# Voltage_source.net
KiCad netlist of a schematic drawn in Altium Designer
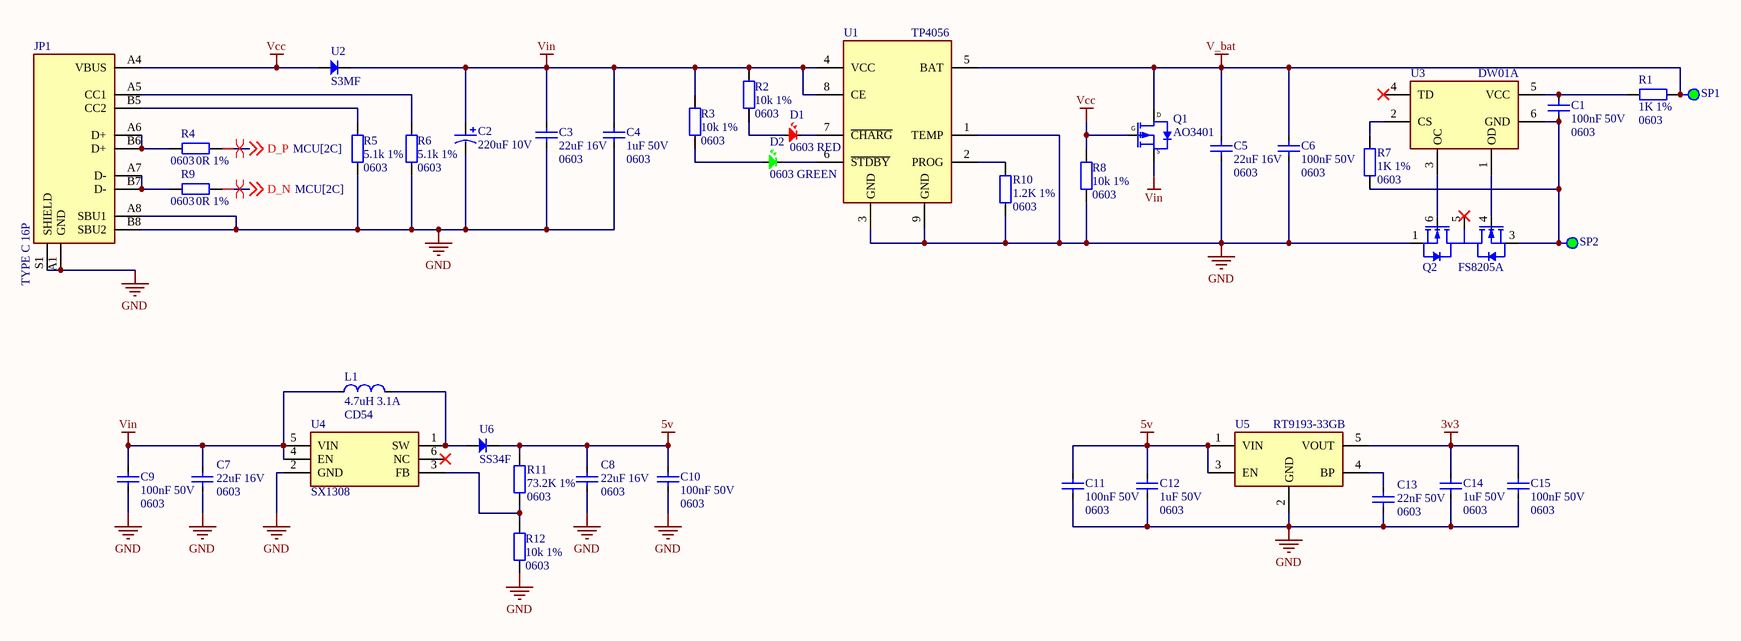
[diagram p0: Voltage_source.SchDoc]

(export (version "E")
  (design (tool "Eeschema 10.0.6"))
  (components
    (comp (ref "C1")
      (value "100nF 50V")
      (footprint "C_0603")
      (description "50V 100nF X7R ±10% 0603 Multilayer Ceramic Capacitors MLCC - SMD/SMT ROHS")
      (fields
        (field (name "MANUFACTURER") "YAGEO")
        (field (name "MRF.PART") "CC0603KRX7R9BB104")
        (field (name "PACKAGE") "0603")
      )
      (libsource (lib "binhbinh") (part "C0603_MLCC_100nF_50V"))
    )
    (comp (ref "C2")
      (value "220uF 10V")
      (footprint "CAP-ALU-SMD-D-NEW")
      (description "220uF 10V ±20% SMD,D6.3xL7.7mm Aluminum Electrolytic Capacitors - SMD ROHS")
      (fields (field (name "MANUFACTURER") "Honor Elec") (field (name "MRF.PART") "RVT1A221M0607"))
      (libsource (lib "binhbinh") (part "C_ALU_220uF_10V_D"))
    )
    (comp (ref "C3")
      (value "22uF 16V")
      (footprint "C_0603")
      (description "16V 22uF X5R ±20% 0603 Multilayer Ceramic Capacitors MLCC - SMD/SMT ROHS")
      (fields
        (field (name "MANUFACTURER") "Samsung Electro-Mechanics")
        (field (name "MRF.PART") "CL10A226MO7JZNC")
        (field (name "PACKAGE") "0603")
      )
      (libsource (lib "binhbinh") (part "C0603_MLCC_22uF_16V"))
    )
    (comp (ref "C4")
      (value "1uF 50V")
      (footprint "C_0603")
      (description "1 µF ±10% 50V Ceramic Capacitor X5R 0603 (1608 Metric)")
      (fields
        (field (name "MANUFACTURER") "Murata Electronics")
        (field (name "MRF.PART") "GRT188R61H105KE13D")
        (field (name "PACKAGE") "0603")
      )
      (libsource (lib "binhbinh") (part "C0603_MLCC_1uF_50V"))
    )
    (comp (ref "C5")
      (value "22uF 16V")
      (footprint "C_0603")
      (description "16V 22uF X5R ±20% 0603 Multilayer Ceramic Capacitors MLCC - SMD/SMT ROHS")
      (fields
        (field (name "MANUFACTURER") "Samsung Electro-Mechanics")
        (field (name "MRF.PART") "CL10A226MO7JZNC")
        (field (name "PACKAGE") "0603")
      )
      (libsource (lib "binhbinh") (part "C0603_MLCC_22uF_16V"))
    )
    (comp (ref "C6")
      (value "100nF 50V")
      (footprint "C_0603")
      (description "50V 100nF X7R ±10% 0603 Multilayer Ceramic Capacitors MLCC - SMD/SMT ROHS")
      (fields
        (field (name "MANUFACTURER") "YAGEO")
        (field (name "MRF.PART") "CC0603KRX7R9BB104")
        (field (name "PACKAGE") "0603")
      )
      (libsource (lib "binhbinh") (part "C0603_MLCC_100nF_50V"))
    )
    (comp (ref "C7")
      (value "22uF 16V")
      (footprint "C_0603")
      (description "16V 22uF X5R ±20% 0603 Multilayer Ceramic Capacitors MLCC - SMD/SMT ROHS")
      (fields
        (field (name "MANUFACTURER") "Samsung Electro-Mechanics")
        (field (name "MRF.PART") "CL10A226MO7JZNC")
        (field (name "PACKAGE") "0603")
      )
      (libsource (lib "binhbinh") (part "C0603_MLCC_22uF_16V"))
    )
    (comp (ref "C8")
      (value "22uF 16V")
      (footprint "C_0603")
      (description "16V 22uF X5R ±20% 0603 Multilayer Ceramic Capacitors MLCC - SMD/SMT ROHS")
      (fields
        (field (name "MANUFACTURER") "Samsung Electro-Mechanics")
        (field (name "MRF.PART") "CL10A226MO7JZNC")
        (field (name "PACKAGE") "0603")
      )
      (libsource (lib "binhbinh") (part "C0603_MLCC_22uF_16V"))
    )
    (comp (ref "C9")
      (value "100nF 50V")
      (footprint "C_0603")
      (description "50V 100nF X7R ±10% 0603 Multilayer Ceramic Capacitors MLCC - SMD/SMT ROHS")
      (fields
        (field (name "MANUFACTURER") "YAGEO")
        (field (name "MRF.PART") "CC0603KRX7R9BB104")
        (field (name "PACKAGE") "0603")
      )
      (libsource (lib "binhbinh") (part "C0603_MLCC_100nF_50V"))
    )
    (comp (ref "C10")
      (value "100nF 50V")
      (footprint "C_0603")
      (description "50V 100nF X7R ±10% 0603 Multilayer Ceramic Capacitors MLCC - SMD/SMT ROHS")
      (fields
        (field (name "MANUFACTURER") "YAGEO")
        (field (name "MRF.PART") "CC0603KRX7R9BB104")
        (field (name "PACKAGE") "0603")
      )
      (libsource (lib "binhbinh") (part "C0603_MLCC_100nF_50V"))
    )
    (comp (ref "C11")
      (value "100nF 50V")
      (footprint "C_0603")
      (description "50V 100nF X7R ±10% 0603 Multilayer Ceramic Capacitors MLCC - SMD/SMT ROHS")
      (fields
        (field (name "MANUFACTURER") "YAGEO")
        (field (name "MRF.PART") "CC0603KRX7R9BB104")
        (field (name "PACKAGE") "0603")
      )
      (libsource (lib "binhbinh") (part "C0603_MLCC_100nF_50V"))
    )
    (comp (ref "C12")
      (value "1uF 50V")
      (footprint "C_0603")
      (description "1 µF ±10% 50V Ceramic Capacitor X5R 0603 (1608 Metric)")
      (fields
        (field (name "MANUFACTURER") "Murata Electronics")
        (field (name "MRF.PART") "GRT188R61H105KE13D")
        (field (name "PACKAGE") "0603")
      )
      (libsource (lib "binhbinh") (part "C0603_MLCC_1uF_50V"))
    )
    (comp (ref "C13")
      (value "22nF 50V")
      (footprint "C_0603")
      (description "50V 22nF X7R ±10% 0603 Multilayer Ceramic Capacitors MLCC - SMD/SMT ROHS")
      (fields
        (field (name "MANUFACTURER") "YAGEO")
        (field (name "MRF.PART") "CC0603KRX7R9BB223")
        (field (name "PACKAGE") "0603")
      )
      (libsource (lib "binhbinh") (part "C0603_MLCC_22nF_50V"))
    )
    (comp (ref "C14")
      (value "1uF 50V")
      (footprint "C_0603")
      (description "1 µF ±10% 50V Ceramic Capacitor X5R 0603 (1608 Metric)")
      (fields
        (field (name "MANUFACTURER") "Murata Electronics")
        (field (name "MRF.PART") "GRT188R61H105KE13D")
        (field (name "PACKAGE") "0603")
      )
      (libsource (lib "binhbinh") (part "C0603_MLCC_1uF_50V"))
    )
    (comp (ref "C15")
      (value "100nF 50V")
      (footprint "C_0603")
      (description "50V 100nF X7R ±10% 0603 Multilayer Ceramic Capacitors MLCC - SMD/SMT ROHS")
      (fields
        (field (name "MANUFACTURER") "YAGEO")
        (field (name "MRF.PART") "CC0603KRX7R9BB104")
        (field (name "PACKAGE") "0603")
      )
      (libsource (lib "binhbinh") (part "C0603_MLCC_100nF_50V"))
    )
    (comp (ref "D1")
      (value "0603 RED")
      (footprint "LED0603_RED")
      (fields (field (name "MANUFACTURER") "XINGLIGHT") (field (name "MRF.PART") "XL-1608SURC-06"))
      (libsource (lib "binhbinh") (part "L0603_RED"))
    )
    (comp (ref "D2")
      (value "0603 GREEN")
      (footprint "LED0603_GREEN")
      (fields (field (name "MANUFACTURER") "Amicc") (field (name "MRF.PART") "A-SP192DGHC-C01-4T"))
      (libsource (lib "binhbinh") (part "L0603_GREEN"))
    )
    (comp (ref "JP1")
      (value "TYPE C 16P")
      (footprint "TYPE C 16P")
      (fields
        (field (name "MANUFACTURER") "Amphenol ICC (Commercial Products)")
        (field (name "MRF.PART") "12402012E212A")
      )
      (libsource (lib "binhbinh") (part "TYPE_C_16P"))
    )
    (comp (ref "L1")
      (value "4.7uH 3.1A")
      (footprint "CD54")
      (description "3.1A 4.7uH ±20% SMD,5.8x5.2mm Power Inductors ROHS")
      (fields
        (field (name "MANUFACTURER") "Ceaiya")
        (field (name "MRF.PART") "CD54-4R7M")
        (field (name "PACKAGE") "CD54")
      )
      (libsource (lib "binhbinh") (part "CD54_4.7uH_3.1A"))
    )
    (comp (ref "Q1")
      (value "AO3401")
      (footprint "SOT23-3")
      (description "30V 4.2A 42mΩ@10V,4A 1.4W 800mV@250uA 1 Piece P-Channel SOT-23 MOSFETs ROHS")
      (fields (field (name "MANUFACTURER") "ElecSuper"))
      (libsource (lib "binhbinh") (part "AO3401"))
    )
    (comp (ref "Q2")
      (value "FS8205A")
      (footprint "SOT23-6")
      (description "20V 25mΩ@2.5V,3A 1.5W 500mV SOT-23-6 MOSFETs ROHS")
      (fields (field (name "MANUFACTURER") "TECH PUBLIC"))
      (libsource (lib "binhbinh") (part "FS8205A"))
    )
    (comp (ref "R1")
      (value "1K 1%")
      (footprint "R_0603")
      (description "1 kOhms ±1% 0.1W, 1/10W Chip Resistor 0603 (1608 Metric) Moisture Resistant Thick Film")
      (fields
        (field (name "MANUFACTURER") "YAGEO")
        (field (name "MRF.PART") "RC0603FR-071KL")
        (field (name "PACKAGE") "0603")
      )
      (libsource (lib "binhbinh") (part "R0603_1K"))
    )
    (comp (ref "R2")
      (value "10k 1%")
      (footprint "R_0603")
      (description "100mW Thick Film Resistor 75V ±100ppm/℃ ±1% 10kΩ 0603 Chip Resistor - Surface Mount ROHS")
      (fields
        (field (name "LCSC PART") "C98220")
        (field (name "MRF.PART") "RC0603FR-0710KL")
        (field (name "PACKAGE") "0603")
      )
      (libsource (lib "binhbinh") (part "R0603_10k"))
    )
    (comp (ref "R3")
      (value "10k 1%")
      (footprint "R_0603")
      (description "100mW Thick Film Resistor 75V ±100ppm/℃ ±1% 10kΩ 0603 Chip Resistor - Surface Mount ROHS")
      (fields
        (field (name "LCSC PART") "C98220")
        (field (name "MRF.PART") "RC0603FR-0710KL")
        (field (name "PACKAGE") "0603")
      )
      (libsource (lib "binhbinh") (part "R0603_10k"))
    )
    (comp (ref "R4")
      (value "0R 1%")
      (footprint "R_0603")
      (description "100mW Thick Film Resistor 75V ±1% 0Ω 0603 Chip Resistor - Surface Mount ROHS")
      (fields
        (field (name "MANUFACTURER") "YAGEO")
        (field (name "MRF.PART") "RC0603FR-070RL")
        (field (name "PACKAGE") "0603")
      )
      (libsource (lib "binhbinh") (part "R0603_0R"))
    )
    (comp (ref "R5")
      (value "5.1k 1%")
      (footprint "R_0603")
      (description "100mW Thick Film Resistor 75V ±100ppm/℃ ±1% 5.1kΩ 0603 Chip Resistor - Surface Mount ROHS")
      (fields
        (field (name "LCSC PART") "C105580")
        (field (name "MRF.PART") "RC0603FR-075K1L")
        (field (name "PACKAGE") "0603")
      )
      (libsource (lib "binhbinh") (part "R0603_5.1k"))
    )
    (comp (ref "R6")
      (value "5.1k 1%")
      (footprint "R_0603")
      (description "100mW Thick Film Resistor 75V ±100ppm/℃ ±1% 5.1kΩ 0603 Chip Resistor - Surface Mount ROHS")
      (fields
        (field (name "LCSC PART") "C105580")
        (field (name "MRF.PART") "RC0603FR-075K1L")
        (field (name "PACKAGE") "0603")
      )
      (libsource (lib "binhbinh") (part "R0603_5.1k"))
    )
    (comp (ref "R7")
      (value "1K 1%")
      (footprint "R_0603")
      (description "1 kOhms ±1% 0.1W, 1/10W Chip Resistor 0603 (1608 Metric) Moisture Resistant Thick Film")
      (fields
        (field (name "MANUFACTURER") "YAGEO")
        (field (name "MRF.PART") "RC0603FR-071KL")
        (field (name "PACKAGE") "0603")
      )
      (libsource (lib "binhbinh") (part "R0603_1K"))
    )
    (comp (ref "R8")
      (value "10k 1%")
      (footprint "R_0603")
      (description "100mW Thick Film Resistor 75V ±100ppm/℃ ±1% 10kΩ 0603 Chip Resistor - Surface Mount ROHS")
      (fields
        (field (name "LCSC PART") "C98220")
        (field (name "MRF.PART") "RC0603FR-0710KL")
        (field (name "PACKAGE") "0603")
      )
      (libsource (lib "binhbinh") (part "R0603_10k"))
    )
    (comp (ref "R9")
      (value "0R 1%")
      (footprint "R_0603")
      (description "100mW Thick Film Resistor 75V ±1% 0Ω 0603 Chip Resistor - Surface Mount ROHS")
      (fields
        (field (name "MANUFACTURER") "YAGEO")
        (field (name "MRF.PART") "RC0603FR-070RL")
        (field (name "PACKAGE") "0603")
      )
      (libsource (lib "binhbinh") (part "R0603_0R"))
    )
    (comp (ref "R10")
      (value "1.2K 1%")
      (footprint "R_0603")
      (description "1.2 kOhms ±1% 0.1W, 1/10W Chip Resistor 0603 (1608 Metric) Moisture Resistant Thick Film")
      (fields
        (field (name "MANUFACTURER") "YAGEO")
        (field (name "MRF.PART") "RC0603FR-071K2L")
        (field (name "PACKAGE") "0603")
      )
      (libsource (lib "binhbinh") (part "R0603_1.2K"))
    )
    (comp (ref "R11")
      (value "73.2K 1%")
      (footprint "R_0603")
      (description "73.2 kOhms ±1% 0.1W, 1/10W Chip Resistor 0603 (1608 Metric) Moisture Resistant Thick Film")
      (fields
        (field (name "MANUFACTURER") "YAGEO")
        (field (name "MRF.PART") "RC0603FR-0773K2L")
        (field (name "PACKAGE") "0603")
      )
      (libsource (lib "binhbinh") (part "R0603_73.2K"))
    )
    (comp (ref "R12")
      (value "10k 1%")
      (footprint "R_0603")
      (description "100mW Thick Film Resistor 75V ±100ppm/℃ ±1% 10kΩ 0603 Chip Resistor - Surface Mount ROHS")
      (fields
        (field (name "LCSC PART") "C98220")
        (field (name "MRF.PART") "RC0603FR-0710KL")
        (field (name "PACKAGE") "0603")
      )
      (libsource (lib "") (part "R0603_10k_1"))
    )
    (comp (ref "SP1")
      (value "SP")
      (footprint "SOLDERING PAD BIG 2")
      (description "Soldering Pad")
      (libsource (lib "IOT SOLUTIONS LOAPAY V5.5.2") (part "SOLDERING PAD"))
    )
    (comp (ref "SP2")
      (value "SP")
      (footprint "SOLDERING PAD BIG 2")
      (description "Soldering Pad")
      (libsource (lib "IOT SOLUTIONS LOAPAY V5.5.2") (part "SOLDERING PAD"))
    )
    (comp (ref "U1")
      (value "TP4056")
      (footprint "ESOP-8")
      (description "ESOP-8 Battery Management ICs ROHS")
      (fields (field (name "MANUFACTURER") "MSKSEMI") (field (name "MRF.PART") "TP4056-MS"))
      (libsource (lib "binhbinh") (part "TP4056"))
    )
    (comp (ref "U2")
      (value "S3MF")
      (footprint "SMAF_L3.5-W2.6-LS4.7-RD")
      (description "3A Independent Type 1.1V@3A 1kV SMAF Diodes - General Purpose ROHS")
      (fields (field (name "MANUFACTURER") "Shandong Jingdao Microelectronics"))
      (libsource (lib "binhbinh") (part "S3MF"))
    )
    (comp (ref "U3")
      (value "DW01A")
      (footprint "SOT23-6")
      (description "1V~5.5V SOT-23-6 Battery Management ROHS")
      (fields (field (name "MANUFACTURER") "PJSEMI") (field (name "LCSC PART") "C41398501"))
      (libsource (lib "binhbinh") (part "DW01A"))
    )
    (comp (ref "U4")
      (value "SX1308")
      (footprint "SOT23-6")
      (description "Boost type Adjustable 28V 2A 2V~24V SOT-23-6 DC-DC Converters ROHS")
      (fields (field (name "MANUFACTURER") "SX(Shenzhen Suosemi Tech)"))
      (libsource (lib "binhbinh") (part "SX1308"))
    )
    (comp (ref "U5")
      (value "RT9193-33GB")
      (footprint "SOT23-5")
      (fields (field (name "MANUFACTURER") "RICHTEK") (field (name "LCSC PART") "C15651"))
      (libsource (lib "binhbinh") (part "RT9193-33GB"))
    )
    (comp (ref "U6")
      (value "SS34F")
      (footprint "SMAF_L3.5-W2.6-LS4.7-RD")
      (description "40V Independent Type 3A 700mV@3A SMAF Schottky Diodes ROHS")
      (fields (field (name "MANUFACTURER") "HXY MOSFET"))
      (libsource (lib "binhbinh") (part "SS34F"))
    )
  )
  (nets
    (net (code "1") (name "3v3") (class "Default")
      (node (ref "C14") (pin "2") (pinfunction "2_2") (pintype "passive"))
      (node (ref "C15") (pin "2") (pinfunction "2_2") (pintype "passive"))
      (node (ref "U5") (pin "5") (pinfunction "VOUT_5") (pintype "passive"))
    )
    (net (code "2") (name "5v") (class "Default")
      (node (ref "C10") (pin "2") (pinfunction "2_2") (pintype "passive"))
      (node (ref "C11") (pin "2") (pinfunction "2_2") (pintype "passive"))
      (node (ref "C12") (pin "2") (pinfunction "2_2") (pintype "passive"))
      (node (ref "C8") (pin "2") (pinfunction "2_2") (pintype "passive"))
      (node (ref "R11") (pin "2") (pinfunction "2_2") (pintype "passive"))
      (node (ref "U5") (pin "1") (pinfunction "VIN_1") (pintype "passive"))
      (node (ref "U5") (pin "3") (pinfunction "EN_3") (pintype "passive"))
      (node (ref "U6") (pin "1") (pinfunction "1_1") (pintype "passive"))
    )
    (net (code "3") (name "D_N") (class "Default")
      (node (ref "R9") (pin "2") (pinfunction "2_2") (pintype "passive"))
    )
    (net (code "4") (name "D_P") (class "Default")
      (node (ref "R4") (pin "2") (pinfunction "2_2") (pintype "passive"))
    )
    (net (code "5") (name "GND") (class "Default")
      (node (ref "C10") (pin "1") (pinfunction "1_1") (pintype "passive"))
      (node (ref "C11") (pin "1") (pinfunction "1_1") (pintype "passive"))
      (node (ref "C12") (pin "1") (pinfunction "1_1") (pintype "passive"))
      (node (ref "C13") (pin "1") (pinfunction "1_1") (pintype "passive"))
      (node (ref "C14") (pin "1") (pinfunction "1_1") (pintype "passive"))
      (node (ref "C15") (pin "1") (pinfunction "1_1") (pintype "passive"))
      (node (ref "C2") (pin "2") (pinfunction "2_2") (pintype "passive"))
      (node (ref "C3") (pin "1") (pinfunction "1_1") (pintype "passive"))
      (node (ref "C4") (pin "1") (pinfunction "1_1") (pintype "passive"))
      (node (ref "C5") (pin "1") (pinfunction "1_1") (pintype "passive"))
      (node (ref "C6") (pin "1") (pinfunction "1_1") (pintype "passive"))
      (node (ref "C7") (pin "1") (pinfunction "1_1") (pintype "passive"))
      (node (ref "C8") (pin "1") (pinfunction "1_1") (pintype "passive"))
      (node (ref "C9") (pin "1") (pinfunction "1_1") (pintype "passive"))
      (node (ref "JP1") (pin "A1") (pinfunction "GND_A1") (pintype "passive"))
      (node (ref "JP1") (pin "A8") (pinfunction "SBU1_A8") (pintype "passive"))
      (node (ref "JP1") (pin "B8") (pinfunction "SBU2_B8") (pintype "passive"))
      (node (ref "JP1") (pin "S1") (pinfunction "SHIELD_S1") (pintype "passive"))
      (node (ref "Q2") (pin "1") (pinfunction "S1_1") (pintype "passive"))
      (node (ref "R10") (pin "1") (pinfunction "1_1") (pintype "passive"))
      (node (ref "R12") (pin "1") (pinfunction "1_1") (pintype "passive"))
      (node (ref "R5") (pin "1") (pinfunction "1_1") (pintype "passive"))
      (node (ref "R6") (pin "1") (pinfunction "1_1") (pintype "passive"))
      (node (ref "R8") (pin "2") (pinfunction "2_2") (pintype "passive"))
      (node (ref "U1") (pin "1") (pinfunction "TEMP_1") (pintype "passive"))
      (node (ref "U1") (pin "3") (pinfunction "GND_3") (pintype "passive"))
      (node (ref "U1") (pin "9") (pinfunction "GND_9") (pintype "passive"))
      (node (ref "U4") (pin "2") (pinfunction "GND_2") (pintype "passive"))
      (node (ref "U5") (pin "2") (pinfunction "GND_2") (pintype "passive"))
    )
    (net (code "6") (name "Net-(D1-Pad1)") (class "Default")
      (node (ref "D1") (pin "1") (pinfunction "1_1") (pintype "passive"))
      (node (ref "R2") (pin "2") (pinfunction "2_2") (pintype "passive"))
    )
    (net (code "7") (name "Net-(D2-Pad1)") (class "Default")
      (node (ref "D2") (pin "1") (pinfunction "1_1") (pintype "passive"))
      (node (ref "R3") (pin "2") (pinfunction "2_2") (pintype "passive"))
    )
    (net (code "8") (name "Net-(JP1-CC1)") (class "Default")
      (node (ref "JP1") (pin "A5") (pinfunction "CC1_A5") (pintype "passive"))
      (node (ref "R6") (pin "2") (pinfunction "2_2") (pintype "passive"))
    )
    (net (code "9") (name "Net-(JP1-CC2)") (class "Default")
      (node (ref "JP1") (pin "B5") (pinfunction "CC2_B5") (pintype "passive"))
      (node (ref "R5") (pin "2") (pinfunction "2_2") (pintype "passive"))
    )
    (net (code "10") (name "Net-(JP1-D+-PadA6)") (class "Default")
      (node (ref "JP1") (pin "A6") (pinfunction "D+_A6") (pintype "passive"))
      (node (ref "JP1") (pin "B6") (pinfunction "D+_B6") (pintype "passive"))
      (node (ref "R4") (pin "1") (pinfunction "1_1") (pintype "passive"))
    )
    (net (code "11") (name "Net-(JP1-D--PadA7)") (class "Default")
      (node (ref "JP1") (pin "A7") (pinfunction "D-_A7") (pintype "passive"))
      (node (ref "JP1") (pin "B7") (pinfunction "D-_B7") (pintype "passive"))
      (node (ref "R9") (pin "1") (pinfunction "1_1") (pintype "passive"))
    )
    (net (code "12") (name "Net-(Q2-G1)") (class "Default")
      (node (ref "Q2") (pin "6") (pinfunction "G1_6") (pintype "passive"))
      (node (ref "U3") (pin "3") (pinfunction "OC_3") (pintype "passive"))
    )
    (net (code "13") (name "Net-(Q2-G2)") (class "Default")
      (node (ref "Q2") (pin "4") (pinfunction "G2_4") (pintype "passive"))
      (node (ref "U3") (pin "1") (pinfunction "OD_1") (pintype "passive"))
    )
    (net (code "14") (name "Net-(Q2-S2)") (class "Default")
      (node (ref "C1") (pin "1") (pinfunction "1_1") (pintype "passive"))
      (node (ref "Q2") (pin "3") (pinfunction "S2_3") (pintype "passive"))
      (node (ref "R7") (pin "1") (pinfunction "1_1") (pintype "passive"))
      (node (ref "SP2") (pin "1") (pinfunction "1_1") (pintype "passive"))
      (node (ref "U3") (pin "6") (pinfunction "GND_6") (pintype "passive"))
    )
    (net (code "15") (name "Net-(U1-PROG)") (class "Default")
      (node (ref "R10") (pin "2") (pinfunction "2_2") (pintype "passive"))
      (node (ref "U1") (pin "2") (pinfunction "PROG_2") (pintype "passive"))
    )
    (net (code "16") (name "Net-(U1-~{CHARG})") (class "Default")
      (node (ref "D1") (pin "2") (pinfunction "2_2") (pintype "passive"))
      (node (ref "U1") (pin "7") (pinfunction "~{CHARG}_7") (pintype "passive"))
    )
    (net (code "17") (name "Net-(U1-~{STDBY})") (class "Default")
      (node (ref "D2") (pin "2") (pinfunction "2_2") (pintype "passive"))
      (node (ref "U1") (pin "6") (pinfunction "~{STDBY}_6") (pintype "passive"))
    )
    (net (code "18") (name "Net-(U3-CS)") (class "Default")
      (node (ref "R7") (pin "2") (pinfunction "2_2") (pintype "passive"))
      (node (ref "U3") (pin "2") (pinfunction "CS_2") (pintype "passive"))
    )
    (net (code "19") (name "Net-(U3-VCC)") (class "Default")
      (node (ref "C1") (pin "2") (pinfunction "2_2") (pintype "passive"))
      (node (ref "R1") (pin "1") (pinfunction "1_1") (pintype "passive"))
      (node (ref "U3") (pin "5") (pinfunction "VCC_5") (pintype "passive"))
    )
    (net (code "20") (name "Net-(U4-FB)") (class "Default")
      (node (ref "R11") (pin "1") (pinfunction "1_1") (pintype "passive"))
      (node (ref "R12") (pin "2") (pinfunction "2_2") (pintype "passive"))
      (node (ref "U4") (pin "3") (pinfunction "FB_3") (pintype "passive"))
    )
    (net (code "21") (name "Net-(U4-SW)") (class "Default")
      (node (ref "L1") (pin "2") (pinfunction "2_2") (pintype "passive"))
      (node (ref "U4") (pin "1") (pinfunction "SW_1") (pintype "passive"))
      (node (ref "U6") (pin "2") (pinfunction "2_2") (pintype "passive"))
    )
    (net (code "22") (name "Net-(U5-BP)") (class "Default")
      (node (ref "C13") (pin "2") (pinfunction "2_2") (pintype "passive"))
      (node (ref "U5") (pin "4") (pinfunction "BP_4") (pintype "passive"))
    )
    (net (code "23") (name "V_bat") (class "Default")
      (node (ref "C5") (pin "2") (pinfunction "2_2") (pintype "passive"))
      (node (ref "C6") (pin "2") (pinfunction "2_2") (pintype "passive"))
      (node (ref "Q1") (pin "3") (pinfunction "D_3") (pintype "passive"))
      (node (ref "R1") (pin "2") (pinfunction "2_2") (pintype "passive"))
      (node (ref "SP1") (pin "1") (pinfunction "1_1") (pintype "passive"))
      (node (ref "U1") (pin "5") (pinfunction "BAT_5") (pintype "passive"))
    )
    (net (code "24") (name "Vcc") (class "Default")
      (node (ref "JP1") (pin "A4") (pinfunction "VBUS_A4") (pintype "passive"))
      (node (ref "Q1") (pin "1") (pinfunction "G_1") (pintype "passive"))
      (node (ref "R8") (pin "1") (pinfunction "1_1") (pintype "passive"))
      (node (ref "U2") (pin "2") (pinfunction "2_2") (pintype "passive"))
    )
    (net (code "25") (name "Vin") (class "Default")
      (node (ref "C2") (pin "1") (pinfunction "1_1") (pintype "passive"))
      (node (ref "C3") (pin "2") (pinfunction "2_2") (pintype "passive"))
      (node (ref "C4") (pin "2") (pinfunction "2_2") (pintype "passive"))
      (node (ref "C7") (pin "2") (pinfunction "2_2") (pintype "passive"))
      (node (ref "C9") (pin "2") (pinfunction "2_2") (pintype "passive"))
      (node (ref "L1") (pin "1") (pinfunction "1_1") (pintype "passive"))
      (node (ref "Q1") (pin "2") (pinfunction "S_2") (pintype "passive"))
      (node (ref "R2") (pin "1") (pinfunction "1_1") (pintype "passive"))
      (node (ref "R3") (pin "1") (pinfunction "1_1") (pintype "passive"))
      (node (ref "U1") (pin "4") (pinfunction "VCC_4") (pintype "passive"))
      (node (ref "U1") (pin "8") (pinfunction "CE_8") (pintype "passive"))
      (node (ref "U2") (pin "1") (pinfunction "1_1") (pintype "passive"))
      (node (ref "U4") (pin "4") (pinfunction "EN_4") (pintype "passive"))
      (node (ref "U4") (pin "5") (pinfunction "VIN_5") (pintype "passive"))
    )
    (net (code "26") (name "unconnected-(Q2-D1{slash}D2-Pad5)") (class "Default")
      (node (ref "Q2") (pin "5") (pinfunction "D1/D2_5") (pintype "passive+no_connect"))
    )
    (net (code "27") (name "unconnected-(U3-TD-Pad4)") (class "Default")
      (node (ref "U3") (pin "4") (pinfunction "TD_4") (pintype "passive+no_connect"))
    )
    (net (code "28") (name "unconnected-(U4-NC-Pad6)") (class "Default")
      (node (ref "U4") (pin "6") (pinfunction "NC_6") (pintype "passive+no_connect"))
    )
  )
)
